# RatDBS-TrackBattery.net
KiCad netlist of a schematic drawn in EAGLE
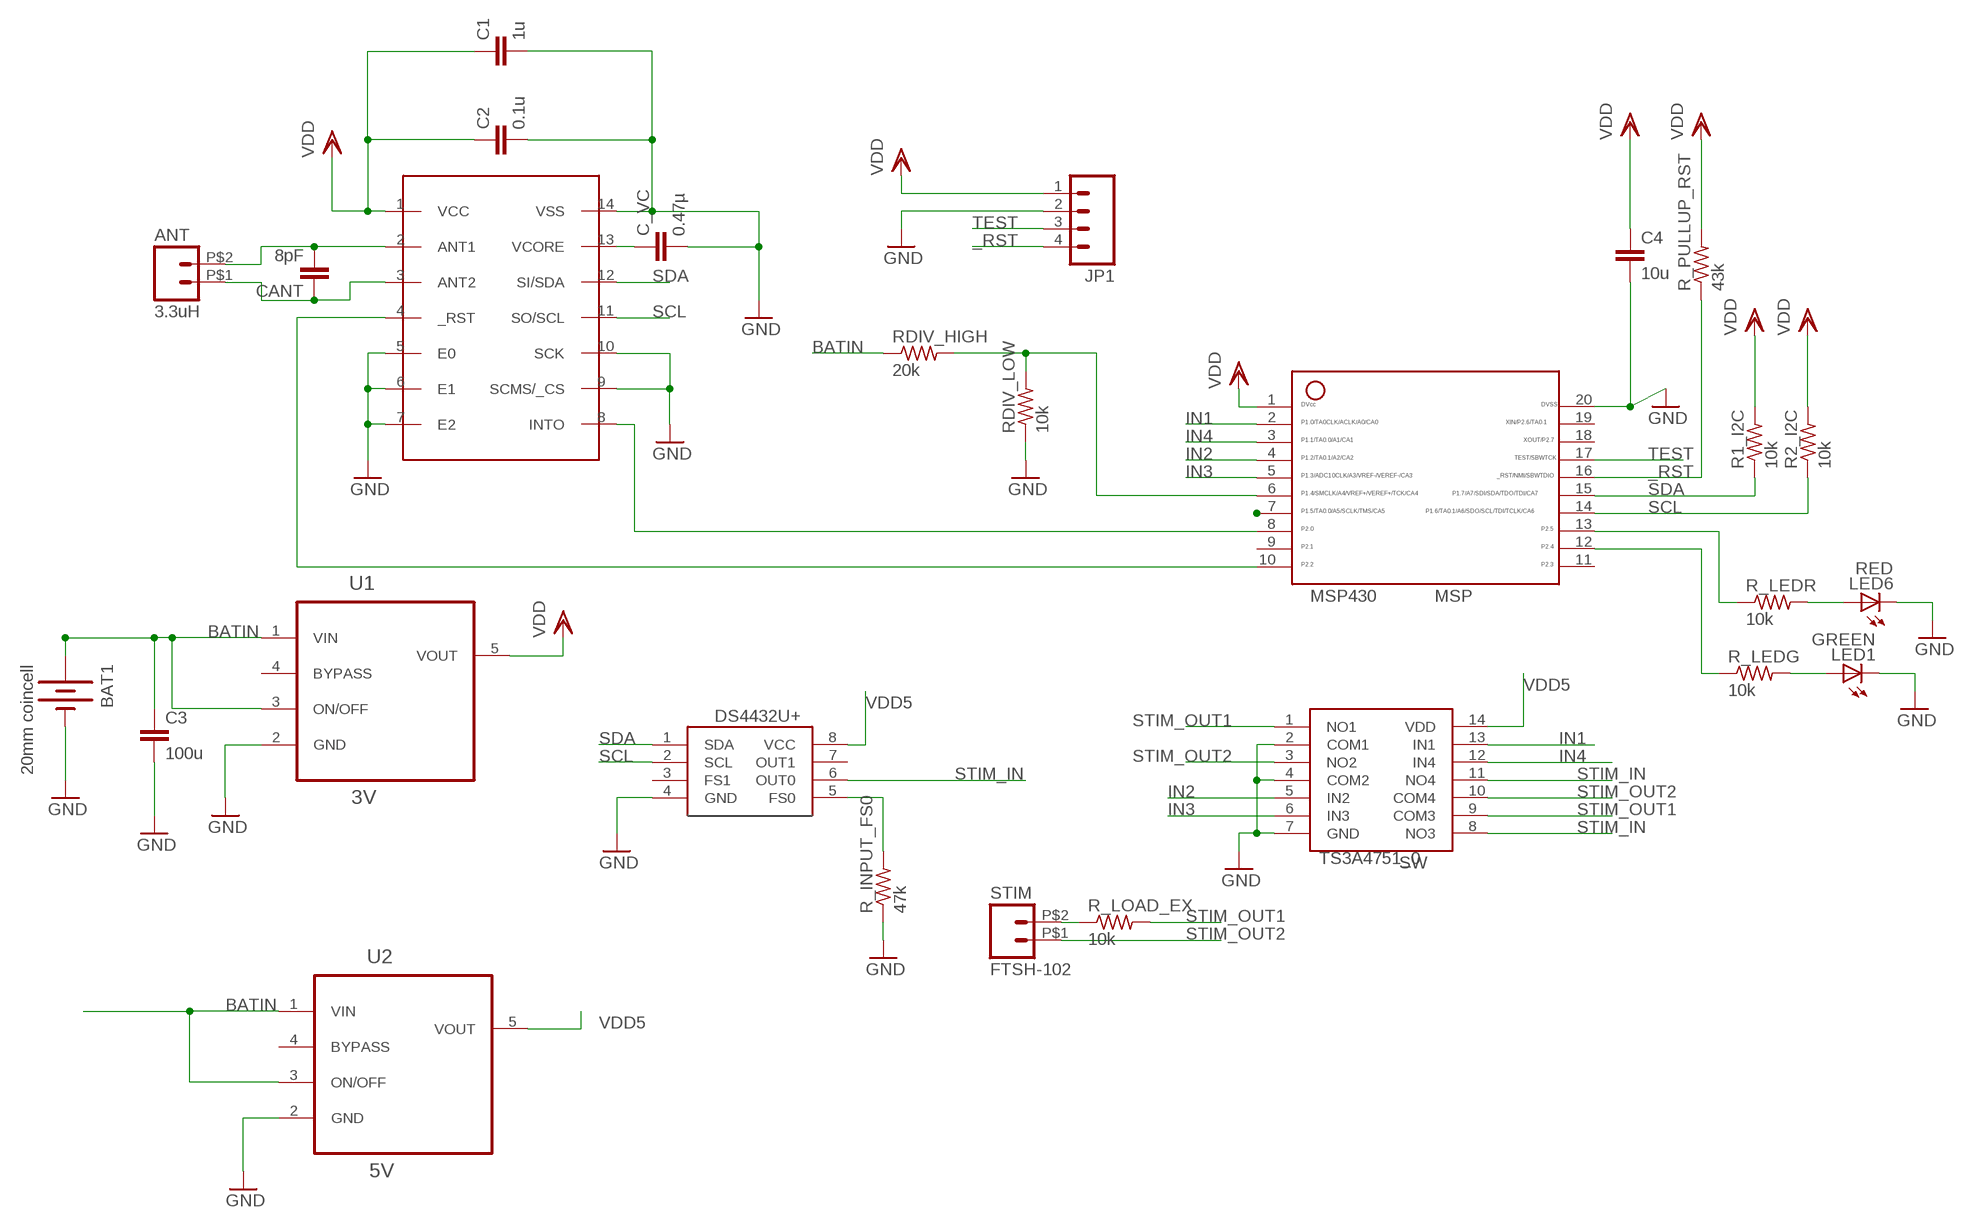
[diagram p0: schematic, sheet 1]

(export (version "E")
  (design (tool "Eeschema 10.0.6"))
  (components
    (comp (ref "ANT")
      (value "3.3uH")
      (footprint "eagle-import:FTSH-102-DH")
      (libsource (lib "eagle-import") (part "FTSH-102"))
    )
    (comp (ref "BAT1")
      (value "20mm coincell")
      (footprint "eagle-import:BATTCOM_20MM_PLASTIC_STUDS")
      (libsource (lib "eagle-import") (part "BATTERY"))
    )
    (comp (ref "C1")
      (value "1u")
      (footprint "eagle-import:C0603")
      (libsource (lib "eagle-import") (part "C-EUC0603"))
    )
    (comp (ref "C2")
      (value "0.1u")
      (footprint "eagle-import:C0603")
      (libsource (lib "eagle-import") (part "C-EUC0603"))
    )
    (comp (ref "C3")
      (value "100u")
      (footprint "eagle-import:C1206")
      (libsource (lib "eagle-import") (part "C-EUC1206"))
    )
    (comp (ref "C4")
      (value "10u")
      (footprint "eagle-import:C1206")
      (libsource (lib "eagle-import") (part "C-EUC1206"))
    )
    (comp (ref "CANT")
      (value "8pF")
      (footprint "eagle-import:C0603")
      (libsource (lib "eagle-import") (part "C-EUC0603"))
    )
    (comp (ref "C_VC")
      (value "0.47µ")
      (footprint "eagle-import:C0603")
      (libsource (lib "eagle-import") (part "C-EUC0603"))
    )
    (comp (ref "DS4432U+")
      (value "DS4432U+")
      (footprint "eagle-import:8_PIN")
      (libsource (lib "eagle-import") (part "DS4432U+"))
    )
    (comp (ref "JP1")
      (value "M041.27MM")
      (footprint "eagle-import:1X04-1.27MM")
      (libsource (lib "eagle-import") (part "M041.27MM"))
    )
    (comp (ref "LED1")
      (value "GREEN")
      (footprint "eagle-import:LED-1206")
      (libsource (lib "eagle-import") (part "LED1206"))
    )
    (comp (ref "LED6")
      (value "RED")
      (footprint "eagle-import:LED-1206")
      (libsource (lib "eagle-import") (part "LED1206"))
    )
    (comp (ref "MSP430")
      (value "MSP")
      (footprint "eagle-import:20_PIN")
      (libsource (lib "eagle-import") (part "MSP430"))
    )
    (comp (ref "R1_I2C")
      (value "10k")
      (footprint "eagle-import:R0603")
      (libsource (lib "eagle-import") (part "R-US_R0603"))
    )
    (comp (ref "R2_I2C")
      (value "10k")
      (footprint "eagle-import:R0603")
      (libsource (lib "eagle-import") (part "R-US_R0603"))
    )
    (comp (ref "RDIV_HIGH")
      (value "20k")
      (footprint "eagle-import:R0603")
      (libsource (lib "eagle-import") (part "R-US_R0603"))
    )
    (comp (ref "RDIV_LOW")
      (value "10k")
      (footprint "eagle-import:R0603")
      (libsource (lib "eagle-import") (part "R-US_R0603"))
    )
    (comp (ref "R_INPUT_FS0")
      (value "47k")
      (footprint "eagle-import:R0603")
      (libsource (lib "eagle-import") (part "R-US_R0603"))
    )
    (comp (ref "R_LEDG")
      (value "10k")
      (footprint "eagle-import:R0603")
      (libsource (lib "eagle-import") (part "R-US_R0603"))
    )
    (comp (ref "R_LEDR")
      (value "10k")
      (footprint "eagle-import:R0603")
      (libsource (lib "eagle-import") (part "R-US_R0603"))
    )
    (comp (ref "R_LOAD_EX")
      (value "10k")
      (footprint "eagle-import:R0603")
      (libsource (lib "eagle-import") (part "R-US_R0603"))
    )
    (comp (ref "R_PULLUP_RST")
      (value "43k")
      (footprint "eagle-import:R0603")
      (libsource (lib "eagle-import") (part "R-US_R0603"))
    )
    (comp (ref "STIM")
      (value "FTSH-102")
      (footprint "eagle-import:FTSH-102-DH")
      (libsource (lib "eagle-import") (part "FTSH-102"))
    )
    (comp (ref "TS3A4751_0")
      (value "SW")
      (footprint "eagle-import:14_PIN")
      (libsource (lib "eagle-import") (part "TS3A4751"))
    )
    (comp (ref "U$1")
      (value "NFC")
      (footprint "eagle-import:PW_R-PDSO-G14")
      (libsource (lib "eagle-import") (part "RF430CL330H"))
    )
    (comp (ref "U1")
      (value "3V")
      (footprint "eagle-import:SOT95P280X145-5N")
      (fields (field (name "MPN") "LP2985A-33DBVTE4"))
      (libsource (lib "eagle-import") (part "LP2985A-33DBVTE4"))
    )
    (comp (ref "U2")
      (value "5V")
      (footprint "eagle-import:SOT95P280X145-5N")
      (fields (field (name "MPN") "LP2985A-33DBVTE4"))
      (libsource (lib "eagle-import") (part "LP2985A-33DBVTE4"))
    )
  )
  (nets
    (net (code "1") (name "/BATIN") (class "Default")
      (node (ref "BAT1") (pin "1") (pinfunction "+_1") (pintype "power_in"))
      (node (ref "C3") (pin "1") (pinfunction "1_1") (pintype "passive"))
      (node (ref "RDIV_HIGH") (pin "1") (pinfunction "1_1") (pintype "passive"))
      (node (ref "U1") (pin "1") (pinfunction "VIN_1") (pintype "power_in"))
      (node (ref "U1") (pin "3") (pinfunction "ON/OFF_3") (pintype "input"))
      (node (ref "U2") (pin "1") (pinfunction "VIN_1") (pintype "power_in"))
      (node (ref "U2") (pin "3") (pinfunction "ON/OFF_3") (pintype "input"))
    )
    (net (code "2") (name "/IN1") (class "Default")
      (node (ref "MSP430") (pin "2") (pinfunction "2_2") (pintype "bidirectional"))
      (node (ref "TS3A4751_0") (pin "13") (pinfunction "IN1_13") (pintype "bidirectional"))
    )
    (net (code "3") (name "/IN2") (class "Default")
      (node (ref "MSP430") (pin "4") (pinfunction "4_4") (pintype "bidirectional"))
      (node (ref "TS3A4751_0") (pin "5") (pinfunction "IN2_5") (pintype "bidirectional"))
    )
    (net (code "4") (name "/IN3") (class "Default")
      (node (ref "MSP430") (pin "5") (pinfunction "5_5") (pintype "bidirectional"))
      (node (ref "TS3A4751_0") (pin "6") (pinfunction "IN3_6") (pintype "bidirectional"))
    )
    (net (code "5") (name "/IN4") (class "Default")
      (node (ref "MSP430") (pin "3") (pinfunction "3_3") (pintype "bidirectional"))
      (node (ref "TS3A4751_0") (pin "12") (pinfunction "IN4_12") (pintype "bidirectional"))
    )
    (net (code "6") (name "/SCL") (class "Default")
      (node (ref "DS4432U+") (pin "2") (pinfunction "SCL_2") (pintype "bidirectional"))
      (node (ref "MSP430") (pin "14") (pinfunction "14_14") (pintype "bidirectional"))
      (node (ref "R2_I2C") (pin "1") (pinfunction "1_1") (pintype "passive"))
      (node (ref "U$1") (pin "11") (pinfunction "SO/SCL_11") (pintype "bidirectional"))
    )
    (net (code "7") (name "/SDA") (class "Default")
      (node (ref "DS4432U+") (pin "1") (pinfunction "SDA_1") (pintype "bidirectional"))
      (node (ref "MSP430") (pin "15") (pinfunction "15_15") (pintype "bidirectional"))
      (node (ref "R1_I2C") (pin "1") (pinfunction "1_1") (pintype "passive"))
      (node (ref "U$1") (pin "12") (pinfunction "SI/SDA_12") (pintype "bidirectional"))
    )
    (net (code "8") (name "/STIM_IN") (class "Default")
      (node (ref "DS4432U+") (pin "6") (pinfunction "OUT0_6") (pintype "bidirectional"))
      (node (ref "TS3A4751_0") (pin "11") (pinfunction "NO4_11") (pintype "bidirectional"))
      (node (ref "TS3A4751_0") (pin "8") (pinfunction "NO3_8") (pintype "bidirectional"))
    )
    (net (code "9") (name "/STIM_OUT1") (class "Default")
      (node (ref "R_LOAD_EX") (pin "2") (pinfunction "2_2") (pintype "passive"))
      (node (ref "TS3A4751_0") (pin "1") (pinfunction "NO1_1") (pintype "bidirectional"))
      (node (ref "TS3A4751_0") (pin "9") (pinfunction "COM3_9") (pintype "bidirectional"))
    )
    (net (code "10") (name "/STIM_OUT2") (class "Default")
      (node (ref "STIM") (pin "P$1") (pinfunction "1_P$1") (pintype "passive"))
      (node (ref "TS3A4751_0") (pin "10") (pinfunction "COM4_10") (pintype "bidirectional"))
      (node (ref "TS3A4751_0") (pin "3") (pinfunction "NO2_3") (pintype "bidirectional"))
    )
    (net (code "11") (name "/TEST") (class "Default")
      (node (ref "JP1") (pin "3") (pinfunction "3_3") (pintype "passive"))
      (node (ref "MSP430") (pin "17") (pinfunction "17_17") (pintype "bidirectional"))
    )
    (net (code "12") (name "/VDD5") (class "Default")
      (node (ref "DS4432U+") (pin "8") (pinfunction "VCC_8") (pintype "power_in"))
      (node (ref "TS3A4751_0") (pin "14") (pinfunction "VDD_14") (pintype "bidirectional"))
      (node (ref "U2") (pin "5") (pinfunction "VOUT_5") (pintype "output"))
    )
    (net (code "13") (name "/_RST") (class "Default")
      (node (ref "JP1") (pin "4") (pinfunction "4_4") (pintype "passive"))
      (node (ref "MSP430") (pin "16") (pinfunction "16_16") (pintype "bidirectional"))
      (node (ref "R_PULLUP_RST") (pin "1") (pinfunction "1_1") (pintype "passive"))
    )
    (net (code "14") (name "GND") (class "Default")
      (node (ref "BAT1") (pin "2") (pinfunction "-_2") (pintype "power_in"))
      (node (ref "C1") (pin "2") (pinfunction "2_2") (pintype "passive"))
      (node (ref "C2") (pin "2") (pinfunction "2_2") (pintype "passive"))
      (node (ref "C3") (pin "2") (pinfunction "2_2") (pintype "passive"))
      (node (ref "C4") (pin "2") (pinfunction "2_2") (pintype "passive"))
      (node (ref "C_VC") (pin "2") (pinfunction "2_2") (pintype "passive"))
      (node (ref "DS4432U+") (pin "4") (pinfunction "GND_4") (pintype "power_in"))
      (node (ref "JP1") (pin "2") (pinfunction "2_2") (pintype "passive"))
      (node (ref "LED1") (pin "C") (pinfunction "C_C") (pintype "passive"))
      (node (ref "LED6") (pin "C") (pinfunction "C_C") (pintype "passive"))
      (node (ref "MSP430") (pin "20") (pinfunction "20_20") (pintype "bidirectional"))
      (node (ref "RDIV_LOW") (pin "1") (pinfunction "1_1") (pintype "passive"))
      (node (ref "R_INPUT_FS0") (pin "1") (pinfunction "1_1") (pintype "passive"))
      (node (ref "TS3A4751_0") (pin "2") (pinfunction "COM1_2") (pintype "bidirectional"))
      (node (ref "TS3A4751_0") (pin "4") (pinfunction "COM2_4") (pintype "bidirectional"))
      (node (ref "TS3A4751_0") (pin "7") (pinfunction "GND_7") (pintype "bidirectional"))
      (node (ref "U$1") (pin "10") (pinfunction "SCK_10") (pintype "bidirectional"))
      (node (ref "U$1") (pin "14") (pinfunction "VSS_14") (pintype "power_in"))
      (node (ref "U$1") (pin "5") (pinfunction "E0_5") (pintype "bidirectional"))
      (node (ref "U$1") (pin "6") (pinfunction "E1_6") (pintype "bidirectional"))
      (node (ref "U$1") (pin "7") (pinfunction "E2_7") (pintype "bidirectional"))
      (node (ref "U$1") (pin "9") (pinfunction "SCMS/_CS_9") (pintype "bidirectional"))
      (node (ref "U1") (pin "2") (pinfunction "GND_2") (pintype "passive"))
      (node (ref "U2") (pin "2") (pinfunction "GND_2") (pintype "passive"))
    )
    (net (code "15") (name "Net-(ANT-1)") (class "Default")
      (node (ref "ANT") (pin "P$1") (pinfunction "1_P$1") (pintype "passive"))
      (node (ref "CANT") (pin "1") (pinfunction "1_1") (pintype "passive"))
      (node (ref "U$1") (pin "3") (pinfunction "ANT2_3") (pintype "bidirectional"))
    )
    (net (code "16") (name "Net-(ANT-2)") (class "Default")
      (node (ref "ANT") (pin "P$2") (pinfunction "2_P$2") (pintype "passive"))
      (node (ref "CANT") (pin "2") (pinfunction "2_2") (pintype "passive"))
      (node (ref "U$1") (pin "2") (pinfunction "ANT1_2") (pintype "bidirectional"))
    )
    (net (code "17") (name "Net-(DS4432U+-FS0)") (class "Default")
      (node (ref "DS4432U+") (pin "5") (pinfunction "FS0_5") (pintype "bidirectional"))
      (node (ref "R_INPUT_FS0") (pin "2") (pinfunction "2_2") (pintype "passive"))
    )
    (net (code "18") (name "Net-(LED1-PadA)") (class "Default")
      (node (ref "LED1") (pin "A") (pinfunction "A_A") (pintype "passive"))
      (node (ref "R_LEDG") (pin "2") (pinfunction "2_2") (pintype "passive"))
    )
    (net (code "19") (name "Net-(LED6-PadA)") (class "Default")
      (node (ref "LED6") (pin "A") (pinfunction "A_A") (pintype "passive"))
      (node (ref "R_LEDR") (pin "2") (pinfunction "2_2") (pintype "passive"))
    )
    (net (code "20") (name "Net-(MSP430-Pad6)") (class "Default")
      (node (ref "MSP430") (pin "6") (pinfunction "6_6") (pintype "bidirectional"))
      (node (ref "RDIV_HIGH") (pin "2") (pinfunction "2_2") (pintype "passive"))
      (node (ref "RDIV_LOW") (pin "2") (pinfunction "2_2") (pintype "passive"))
    )
    (net (code "21") (name "Net-(MSP430-Pad12)") (class "Default")
      (node (ref "MSP430") (pin "12") (pinfunction "12_12") (pintype "bidirectional"))
      (node (ref "R_LEDG") (pin "1") (pinfunction "1_1") (pintype "passive"))
    )
    (net (code "22") (name "Net-(MSP430-Pad13)") (class "Default")
      (node (ref "MSP430") (pin "13") (pinfunction "13_13") (pintype "bidirectional"))
      (node (ref "R_LEDR") (pin "1") (pinfunction "1_1") (pintype "passive"))
    )
    (net (code "23") (name "Net-(STIM-2)") (class "Default")
      (node (ref "R_LOAD_EX") (pin "1") (pinfunction "1_1") (pintype "passive"))
      (node (ref "STIM") (pin "P$2") (pinfunction "2_P$2") (pintype "passive"))
    )
    (net (code "24") (name "Net-(U$1-INTO)") (class "Default")
      (node (ref "MSP430") (pin "8") (pinfunction "8_8") (pintype "bidirectional"))
      (node (ref "U$1") (pin "8") (pinfunction "INTO_8") (pintype "bidirectional"))
    )
    (net (code "25") (name "Net-(U$1-VCORE)") (class "Default")
      (node (ref "C_VC") (pin "1") (pinfunction "1_1") (pintype "passive"))
      (node (ref "U$1") (pin "13") (pinfunction "VCORE_13") (pintype "bidirectional"))
    )
    (net (code "26") (name "Net-(U$1-_RST)") (class "Default")
      (node (ref "MSP430") (pin "10") (pinfunction "10_10") (pintype "bidirectional"))
      (node (ref "U$1") (pin "4") (pinfunction "_RST_4") (pintype "bidirectional"))
    )
    (net (code "27") (name "VDD") (class "Default")
      (node (ref "C1") (pin "1") (pinfunction "1_1") (pintype "passive"))
      (node (ref "C2") (pin "1") (pinfunction "1_1") (pintype "passive"))
      (node (ref "C4") (pin "1") (pinfunction "1_1") (pintype "passive"))
      (node (ref "JP1") (pin "1") (pinfunction "1_1") (pintype "passive"))
      (node (ref "MSP430") (pin "1") (pinfunction "1_1") (pintype "bidirectional"))
      (node (ref "R1_I2C") (pin "2") (pinfunction "2_2") (pintype "passive"))
      (node (ref "R2_I2C") (pin "2") (pinfunction "2_2") (pintype "passive"))
      (node (ref "R_PULLUP_RST") (pin "2") (pinfunction "2_2") (pintype "passive"))
      (node (ref "U$1") (pin "1") (pinfunction "VCC_1") (pintype "power_in"))
      (node (ref "U1") (pin "5") (pinfunction "VOUT_5") (pintype "output"))
    )
    (net (code "28") (name "unconnected-(DS4432U+-FS1-Pad3)") (class "Default")
      (node (ref "DS4432U+") (pin "3") (pinfunction "FS1_3") (pintype "bidirectional"))
    )
    (net (code "29") (name "unconnected-(DS4432U+-OUT1-Pad7)") (class "Default")
      (node (ref "DS4432U+") (pin "7") (pinfunction "OUT1_7") (pintype "bidirectional"))
    )
    (net (code "30") (name "unconnected-(MSP430-Pad7)") (class "Default")
      (node (ref "MSP430") (pin "7") (pinfunction "7_7") (pintype "bidirectional"))
    )
    (net (code "31") (name "unconnected-(MSP430-Pad9)") (class "Default")
      (node (ref "MSP430") (pin "9") (pinfunction "9_9") (pintype "bidirectional"))
    )
    (net (code "32") (name "unconnected-(MSP430-Pad11)") (class "Default")
      (node (ref "MSP430") (pin "11") (pinfunction "11_11") (pintype "bidirectional"))
    )
    (net (code "33") (name "unconnected-(MSP430-Pad18)") (class "Default")
      (node (ref "MSP430") (pin "18") (pinfunction "18_18") (pintype "bidirectional"))
    )
    (net (code "34") (name "unconnected-(MSP430-Pad19)") (class "Default")
      (node (ref "MSP430") (pin "19") (pinfunction "19_19") (pintype "bidirectional"))
    )
    (net (code "35") (name "unconnected-(U1-BYPASS-Pad4)") (class "Default")
      (node (ref "U1") (pin "4") (pinfunction "BYPASS_4") (pintype "input"))
    )
    (net (code "36") (name "unconnected-(U2-BYPASS-Pad4)") (class "Default")
      (node (ref "U2") (pin "4") (pinfunction "BYPASS_4") (pintype "input"))
    )
  )
)
